# dev_board.net
KiCad netlist of a schematic drawn in EAGLE
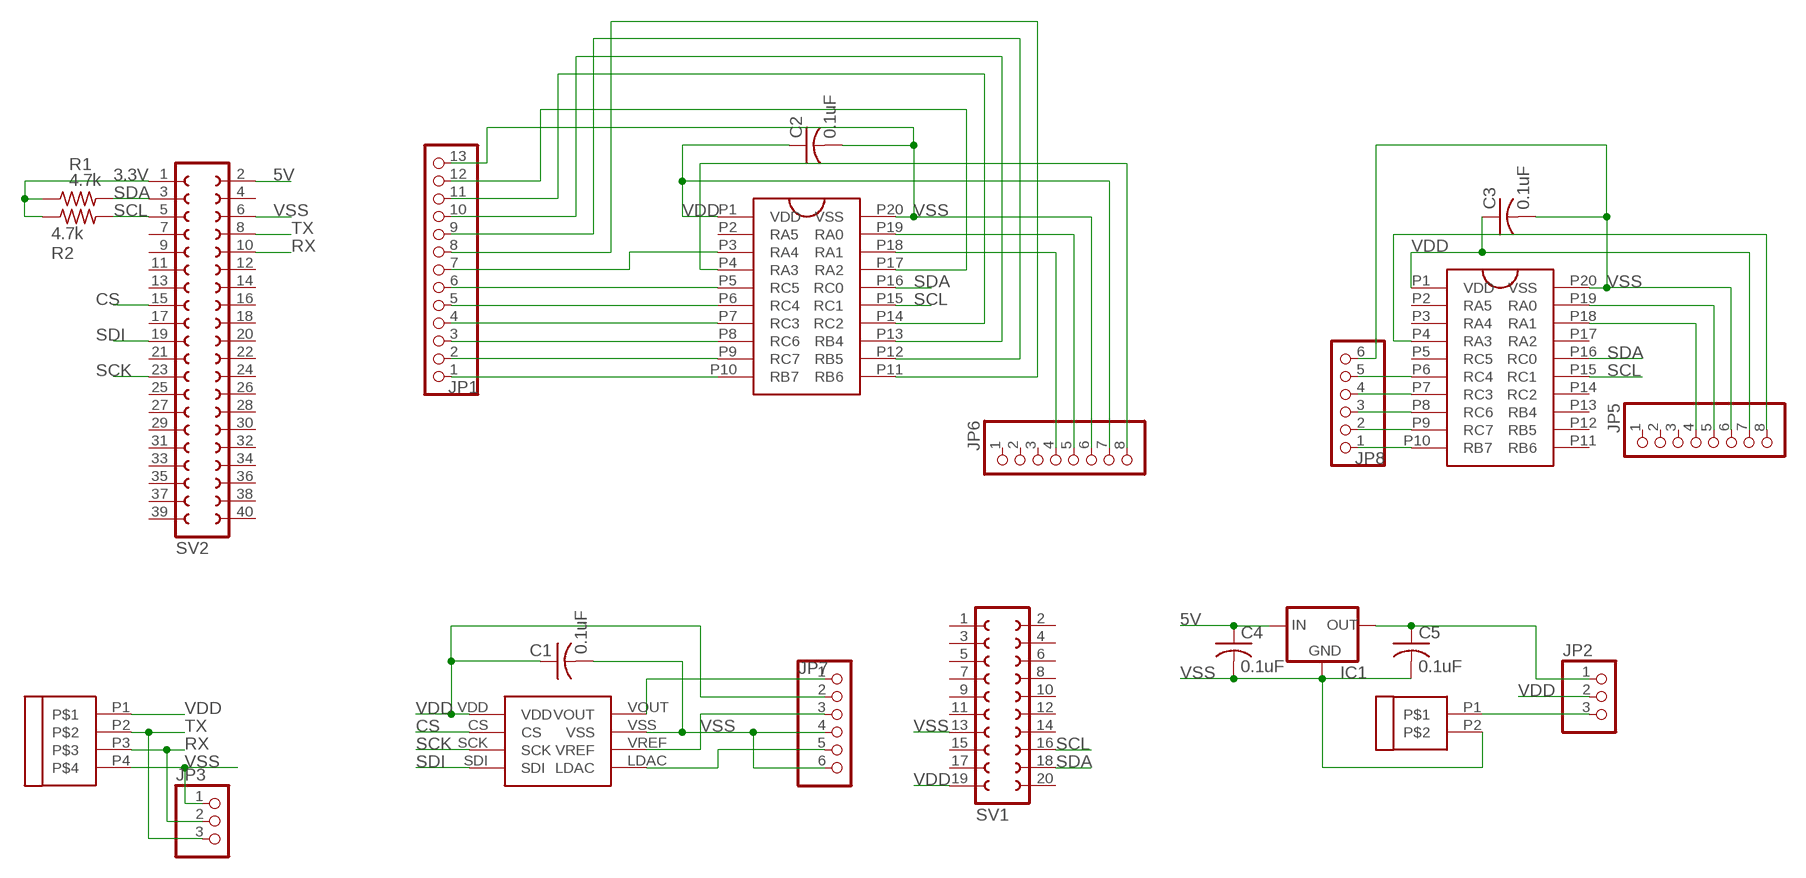
[diagram p0: schematic, sheet 1]

(export (version "E")
  (design (tool "Eeschema 10.0.6"))
  (components
    (comp (ref "C1")
      (value "0.1uF")
      (footprint "eagle-import:C025-030X050")
      (libsource (lib "eagle-import") (part "C-US025-030X050"))
    )
    (comp (ref "C2")
      (value "0.1uF")
      (footprint "eagle-import:C025-030X050")
      (libsource (lib "eagle-import") (part "C-US025-030X050"))
    )
    (comp (ref "C3")
      (value "0.1uF")
      (footprint "eagle-import:C025-030X050")
      (libsource (lib "eagle-import") (part "C-US025-030X050"))
    )
    (comp (ref "C4")
      (value "0.1uF")
      (footprint "eagle-import:C025-030X050")
      (libsource (lib "eagle-import") (part "C-US025-030X050"))
    )
    (comp (ref "C5")
      (value "0.1uF")
      (footprint "eagle-import:C025-030X050")
      (libsource (lib "eagle-import") (part "C-US025-030X050"))
    )
    (comp (ref "IC1")
      (value "MCP1700INLINE")
      (footprint "eagle-import:TO92-INLINE")
      (libsource (lib "eagle-import") (part "MCP1700INLINE"))
    )
    (comp (ref "JP1")
      (value "PINHD-1X13")
      (footprint "eagle-import:1X13")
      (libsource (lib "eagle-import") (part "PINHD-1X13"))
    )
    (comp (ref "JP2")
      (value "PINHD-1X3")
      (footprint "eagle-import:1X03")
      (libsource (lib "eagle-import") (part "PINHD-1X3"))
    )
    (comp (ref "JP3")
      (value "PINHD-1X3")
      (footprint "eagle-import:1X03")
      (libsource (lib "eagle-import") (part "pinhead_325_PINHD-1X3"))
    )
    (comp (ref "JP5")
      (value "PINHD-1X8BIG")
      (footprint "eagle-import:1X08-BIG")
      (libsource (lib "eagle-import") (part "PINHD-1X8BIG"))
    )
    (comp (ref "JP6")
      (value "PINHD-1X8BIG")
      (footprint "eagle-import:1X08-BIG")
      (libsource (lib "eagle-import") (part "PINHD-1X8BIG"))
    )
    (comp (ref "JP7")
      (value "PINHD-1X6")
      (footprint "eagle-import:1X06")
      (libsource (lib "eagle-import") (part "PINHD-1X6"))
    )
    (comp (ref "JP8")
      (value "PINHD-1X6")
      (footprint "eagle-import:1X06")
      (libsource (lib "eagle-import") (part "PINHD-1X6"))
    )
    (comp (ref "R1")
      (value "4.7k")
      (footprint "eagle-import:0207_7")
      (libsource (lib "eagle-import") (part "R-US_0207/7"))
    )
    (comp (ref "R2")
      (value "4.7k")
      (footprint "eagle-import:0207_7")
      (libsource (lib "eagle-import") (part "R-US_0207/7"))
    )
    (comp (ref "SV1")
      (value "FE10-2")
      (footprint "eagle-import:FE10-2")
      (libsource (lib "eagle-import") (part "FE10-2"))
    )
    (comp (ref "SV2")
      (value "FE20-2")
      (footprint "eagle-import:FE20-2")
      (libsource (lib "eagle-import") (part "FE20-2"))
    )
    (comp (ref "U$1")
      (value "MCP4911")
      (footprint "eagle-import:DAC_DIP")
      (libsource (lib "eagle-import") (part "MCP4911"))
    )
    (comp (ref "U$2")
      (value "4TERMBLOCK")
      (footprint "eagle-import:4TERMBLOCK")
      (libsource (lib "eagle-import") (part "4TERMBLOCK"))
    )
    (comp (ref "U$3")
      (value "2TERMBLOCK")
      (footprint "eagle-import:2TERMBLOCK")
      (libsource (lib "eagle-import") (part "2TERMBLOCK"))
    )
    (comp (ref "U1")
      (value "PIC18F15Q40PDIP")
      (footprint "eagle-import:PDIP")
      (libsource (lib "eagle-import") (part "PIC18F15Q40PDIP"))
    )
    (comp (ref "U2")
      (value "PIC18F15Q40PDIP")
      (footprint "eagle-import:PDIP")
      (libsource (lib "eagle-import") (part "PIC18F15Q40PDIP"))
    )
  )
  (nets
    (net (code "1") (name "/3.3V") (class "Default")
      (node (ref "R1") (pin "1") (pinfunction "1_1") (pintype "passive"))
      (node (ref "R2") (pin "1") (pinfunction "1_1") (pintype "passive"))
      (node (ref "SV2") (pin "1") (pinfunction "1_1") (pintype "passive"))
    )
    (net (code "2") (name "/5V") (class "Default")
      (node (ref "C4") (pin "1") (pinfunction "1_1") (pintype "passive"))
      (node (ref "IC1") (pin "2") (pinfunction "IN_2") (pintype "input"))
      (node (ref "SV2") (pin "2") (pinfunction "2_2") (pintype "passive"))
    )
    (net (code "3") (name "/CS") (class "Default")
      (node (ref "SV2") (pin "15") (pinfunction "15_15") (pintype "passive"))
      (node (ref "U$1") (pin "CS") (pinfunction "CS_CS") (pintype "bidirectional"))
    )
    (net (code "4") (name "/RX") (class "Default")
      (node (ref "JP3") (pin "2") (pinfunction "2_2") (pintype "passive"))
      (node (ref "SV2") (pin "10") (pinfunction "10_10") (pintype "passive"))
      (node (ref "U$2") (pin "P3") (pinfunction "P$3_P3") (pintype "bidirectional"))
    )
    (net (code "5") (name "/SCK") (class "Default")
      (node (ref "SV2") (pin "23") (pinfunction "23_23") (pintype "passive"))
      (node (ref "U$1") (pin "SCK") (pinfunction "SCK_SCK") (pintype "bidirectional"))
    )
    (net (code "6") (name "/SCL") (class "Default")
      (node (ref "R2") (pin "2") (pinfunction "2_2") (pintype "passive"))
      (node (ref "SV1") (pin "16") (pinfunction "16_16") (pintype "passive"))
      (node (ref "SV2") (pin "5") (pinfunction "5_5") (pintype "passive"))
      (node (ref "U1") (pin "P15") (pinfunction "RC1_P15") (pintype "bidirectional"))
      (node (ref "U2") (pin "P15") (pinfunction "RC1_P15") (pintype "bidirectional"))
    )
    (net (code "7") (name "/SDA") (class "Default")
      (node (ref "R1") (pin "2") (pinfunction "2_2") (pintype "passive"))
      (node (ref "SV1") (pin "18") (pinfunction "18_18") (pintype "passive"))
      (node (ref "SV2") (pin "3") (pinfunction "3_3") (pintype "passive"))
      (node (ref "U1") (pin "P16") (pinfunction "RC0_P16") (pintype "bidirectional"))
      (node (ref "U2") (pin "P16") (pinfunction "RC0_P16") (pintype "bidirectional"))
    )
    (net (code "8") (name "/SDI") (class "Default")
      (node (ref "SV2") (pin "19") (pinfunction "19_19") (pintype "passive"))
      (node (ref "U$1") (pin "SDI") (pinfunction "SDI_SDI") (pintype "bidirectional"))
    )
    (net (code "9") (name "/TX") (class "Default")
      (node (ref "JP3") (pin "3") (pinfunction "3_3") (pintype "passive"))
      (node (ref "SV2") (pin "8") (pinfunction "8_8") (pintype "passive"))
      (node (ref "U$2") (pin "P2") (pinfunction "P$2_P2") (pintype "bidirectional"))
    )
    (net (code "10") (name "/VDD") (class "Default")
      (node (ref "C1") (pin "1") (pinfunction "1_1") (pintype "passive"))
      (node (ref "C2") (pin "1") (pinfunction "1_1") (pintype "passive"))
      (node (ref "C3") (pin "1") (pinfunction "1_1") (pintype "passive"))
      (node (ref "JP2") (pin "2") (pinfunction "2_2") (pintype "passive"))
      (node (ref "JP5") (pin "7") (pinfunction "7_7") (pintype "passive"))
      (node (ref "JP6") (pin "7") (pinfunction "7_7") (pintype "passive"))
      (node (ref "JP7") (pin "2") (pinfunction "2_2") (pintype "passive"))
      (node (ref "SV1") (pin "19") (pinfunction "19_19") (pintype "passive"))
      (node (ref "U$1") (pin "VDD") (pinfunction "VDD_VDD") (pintype "bidirectional"))
      (node (ref "U$2") (pin "P1") (pinfunction "P$1_P1") (pintype "bidirectional"))
      (node (ref "U1") (pin "P1") (pinfunction "VDD_P1") (pintype "bidirectional"))
      (node (ref "U2") (pin "P1") (pinfunction "VDD_P1") (pintype "bidirectional"))
    )
    (net (code "11") (name "/VSS") (class "Default")
      (node (ref "C1") (pin "2") (pinfunction "2_2") (pintype "passive"))
      (node (ref "C2") (pin "2") (pinfunction "2_2") (pintype "passive"))
      (node (ref "C3") (pin "2") (pinfunction "2_2") (pintype "passive"))
      (node (ref "C4") (pin "2") (pinfunction "2_2") (pintype "passive"))
      (node (ref "C5") (pin "2") (pinfunction "2_2") (pintype "passive"))
      (node (ref "IC1") (pin "1") (pinfunction "GND_1") (pintype "input"))
      (node (ref "JP1") (pin "13") (pinfunction "13_13") (pintype "passive"))
      (node (ref "JP3") (pin "1") (pinfunction "1_1") (pintype "passive"))
      (node (ref "JP5") (pin "6") (pinfunction "6_6") (pintype "passive"))
      (node (ref "JP6") (pin "6") (pinfunction "6_6") (pintype "passive"))
      (node (ref "JP7") (pin "4") (pinfunction "4_4") (pintype "passive"))
      (node (ref "JP7") (pin "6") (pinfunction "6_6") (pintype "passive"))
      (node (ref "JP8") (pin "6") (pinfunction "6_6") (pintype "passive"))
      (node (ref "SV1") (pin "13") (pinfunction "13_13") (pintype "passive"))
      (node (ref "SV2") (pin "6") (pinfunction "6_6") (pintype "passive"))
      (node (ref "U$1") (pin "VSS") (pinfunction "VSS_VSS") (pintype "bidirectional"))
      (node (ref "U$2") (pin "P4") (pinfunction "P$4_P4") (pintype "bidirectional"))
      (node (ref "U$3") (pin "P2") (pinfunction "P$2_P2") (pintype "bidirectional"))
      (node (ref "U1") (pin "P20") (pinfunction "VSS_P20") (pintype "bidirectional"))
      (node (ref "U2") (pin "P20") (pinfunction "VSS_P20") (pintype "bidirectional"))
    )
    (net (code "12") (name "Net-(IC1-OUT)") (class "Default")
      (node (ref "C5") (pin "1") (pinfunction "1_1") (pintype "passive"))
      (node (ref "IC1") (pin "3") (pinfunction "OUT_3") (pintype "passive"))
      (node (ref "JP2") (pin "1") (pinfunction "1_1") (pintype "passive"))
    )
    (net (code "13") (name "Net-(JP7-Pad1)") (class "Default")
      (node (ref "JP7") (pin "1") (pinfunction "1_1") (pintype "passive"))
      (node (ref "U$1") (pin "VOUT") (pinfunction "VOUT_VOUT") (pintype "bidirectional"))
    )
    (net (code "14") (name "Net-(JP7-Pad3)") (class "Default")
      (node (ref "JP7") (pin "3") (pinfunction "3_3") (pintype "passive"))
      (node (ref "U$1") (pin "VREF") (pinfunction "VREF_VREF") (pintype "bidirectional"))
    )
    (net (code "15") (name "Net-(JP7-Pad5)") (class "Default")
      (node (ref "JP7") (pin "5") (pinfunction "5_5") (pintype "passive"))
      (node (ref "U$1") (pin "LDAC") (pinfunction "LDAC_LDAC") (pintype "bidirectional"))
    )
    (net (code "16") (name "Net-(U$3-P$1)") (class "Default")
      (node (ref "JP2") (pin "3") (pinfunction "3_3") (pintype "passive"))
      (node (ref "U$3") (pin "P1") (pinfunction "P$1_P1") (pintype "bidirectional"))
    )
    (net (code "17") (name "Net-(U1-RA0)") (class "Default")
      (node (ref "JP6") (pin "5") (pinfunction "5_5") (pintype "passive"))
      (node (ref "U1") (pin "P19") (pinfunction "RA0_P19") (pintype "bidirectional"))
    )
    (net (code "18") (name "Net-(U1-RA1)") (class "Default")
      (node (ref "JP6") (pin "4") (pinfunction "4_4") (pintype "passive"))
      (node (ref "U1") (pin "P18") (pinfunction "RA1_P18") (pintype "bidirectional"))
    )
    (net (code "19") (name "Net-(U1-RA2)") (class "Default")
      (node (ref "JP1") (pin "12") (pinfunction "12_12") (pintype "passive"))
      (node (ref "U1") (pin "P17") (pinfunction "RA2_P17") (pintype "bidirectional"))
    )
    (net (code "20") (name "Net-(U1-RA3)") (class "Default")
      (node (ref "JP6") (pin "8") (pinfunction "8_8") (pintype "passive"))
      (node (ref "U1") (pin "P4") (pinfunction "RA3_P4") (pintype "bidirectional"))
    )
    (net (code "21") (name "Net-(U1-RA4)") (class "Default")
      (node (ref "JP1") (pin "7") (pinfunction "7_7") (pintype "passive"))
      (node (ref "U1") (pin "P3") (pinfunction "RA4_P3") (pintype "bidirectional"))
    )
    (net (code "22") (name "Net-(U1-RB4)") (class "Default")
      (node (ref "JP1") (pin "10") (pinfunction "10_10") (pintype "passive"))
      (node (ref "U1") (pin "P13") (pinfunction "RB4_P13") (pintype "bidirectional"))
    )
    (net (code "23") (name "Net-(U1-RB5)") (class "Default")
      (node (ref "JP1") (pin "9") (pinfunction "9_9") (pintype "passive"))
      (node (ref "U1") (pin "P12") (pinfunction "RB5_P12") (pintype "bidirectional"))
    )
    (net (code "24") (name "Net-(U1-RB6)") (class "Default")
      (node (ref "JP1") (pin "8") (pinfunction "8_8") (pintype "passive"))
      (node (ref "U1") (pin "P11") (pinfunction "RB6_P11") (pintype "bidirectional"))
    )
    (net (code "25") (name "Net-(U1-RB7)") (class "Default")
      (node (ref "JP1") (pin "1") (pinfunction "1_1") (pintype "passive"))
      (node (ref "U1") (pin "P10") (pinfunction "RB7_P10") (pintype "bidirectional"))
    )
    (net (code "26") (name "Net-(U1-RC2)") (class "Default")
      (node (ref "JP1") (pin "11") (pinfunction "11_11") (pintype "passive"))
      (node (ref "U1") (pin "P14") (pinfunction "RC2_P14") (pintype "bidirectional"))
    )
    (net (code "27") (name "Net-(U1-RC3)") (class "Default")
      (node (ref "JP1") (pin "4") (pinfunction "4_4") (pintype "passive"))
      (node (ref "U1") (pin "P7") (pinfunction "RC3_P7") (pintype "bidirectional"))
    )
    (net (code "28") (name "Net-(U1-RC4)") (class "Default")
      (node (ref "JP1") (pin "5") (pinfunction "5_5") (pintype "passive"))
      (node (ref "U1") (pin "P6") (pinfunction "RC4_P6") (pintype "bidirectional"))
    )
    (net (code "29") (name "Net-(U1-RC5)") (class "Default")
      (node (ref "JP1") (pin "6") (pinfunction "6_6") (pintype "passive"))
      (node (ref "U1") (pin "P5") (pinfunction "RC5_P5") (pintype "bidirectional"))
    )
    (net (code "30") (name "Net-(U1-RC6)") (class "Default")
      (node (ref "JP1") (pin "3") (pinfunction "3_3") (pintype "passive"))
      (node (ref "U1") (pin "P8") (pinfunction "RC6_P8") (pintype "bidirectional"))
    )
    (net (code "31") (name "Net-(U1-RC7)") (class "Default")
      (node (ref "JP1") (pin "2") (pinfunction "2_2") (pintype "passive"))
      (node (ref "U1") (pin "P9") (pinfunction "RC7_P9") (pintype "bidirectional"))
    )
    (net (code "32") (name "Net-(U2-RA0)") (class "Default")
      (node (ref "JP5") (pin "5") (pinfunction "5_5") (pintype "passive"))
      (node (ref "U2") (pin "P19") (pinfunction "RA0_P19") (pintype "bidirectional"))
    )
    (net (code "33") (name "Net-(U2-RA1)") (class "Default")
      (node (ref "JP5") (pin "4") (pinfunction "4_4") (pintype "passive"))
      (node (ref "U2") (pin "P18") (pinfunction "RA1_P18") (pintype "bidirectional"))
    )
    (net (code "34") (name "Net-(U2-RA3)") (class "Default")
      (node (ref "JP5") (pin "8") (pinfunction "8_8") (pintype "passive"))
      (node (ref "U2") (pin "P4") (pinfunction "RA3_P4") (pintype "bidirectional"))
    )
    (net (code "35") (name "Net-(U2-RB7)") (class "Default")
      (node (ref "JP8") (pin "1") (pinfunction "1_1") (pintype "passive"))
      (node (ref "U2") (pin "P10") (pinfunction "RB7_P10") (pintype "bidirectional"))
    )
    (net (code "36") (name "Net-(U2-RC3)") (class "Default")
      (node (ref "JP8") (pin "4") (pinfunction "4_4") (pintype "passive"))
      (node (ref "U2") (pin "P7") (pinfunction "RC3_P7") (pintype "bidirectional"))
    )
    (net (code "37") (name "Net-(U2-RC4)") (class "Default")
      (node (ref "JP8") (pin "5") (pinfunction "5_5") (pintype "passive"))
      (node (ref "U2") (pin "P6") (pinfunction "RC4_P6") (pintype "bidirectional"))
    )
    (net (code "38") (name "Net-(U2-RC6)") (class "Default")
      (node (ref "JP8") (pin "3") (pinfunction "3_3") (pintype "passive"))
      (node (ref "U2") (pin "P8") (pinfunction "RC6_P8") (pintype "bidirectional"))
    )
    (net (code "39") (name "Net-(U2-RC7)") (class "Default")
      (node (ref "JP8") (pin "2") (pinfunction "2_2") (pintype "passive"))
      (node (ref "U2") (pin "P9") (pinfunction "RC7_P9") (pintype "bidirectional"))
    )
    (net (code "40") (name "unconnected-(JP5-Pad1)") (class "Default")
      (node (ref "JP5") (pin "1") (pinfunction "1_1") (pintype "passive"))
    )
    (net (code "41") (name "unconnected-(JP5-Pad2)") (class "Default")
      (node (ref "JP5") (pin "2") (pinfunction "2_2") (pintype "passive"))
    )
    (net (code "42") (name "unconnected-(JP5-Pad3)") (class "Default")
      (node (ref "JP5") (pin "3") (pinfunction "3_3") (pintype "passive"))
    )
    (net (code "43") (name "unconnected-(JP6-Pad1)") (class "Default")
      (node (ref "JP6") (pin "1") (pinfunction "1_1") (pintype "passive"))
    )
    (net (code "44") (name "unconnected-(JP6-Pad2)") (class "Default")
      (node (ref "JP6") (pin "2") (pinfunction "2_2") (pintype "passive"))
    )
    (net (code "45") (name "unconnected-(JP6-Pad3)") (class "Default")
      (node (ref "JP6") (pin "3") (pinfunction "3_3") (pintype "passive"))
    )
    (net (code "46") (name "unconnected-(SV1-Pad1)") (class "Default")
      (node (ref "SV1") (pin "1") (pinfunction "1_1") (pintype "passive"))
    )
    (net (code "47") (name "unconnected-(SV1-Pad2)") (class "Default")
      (node (ref "SV1") (pin "2") (pinfunction "2_2") (pintype "passive"))
    )
    (net (code "48") (name "unconnected-(SV1-Pad3)") (class "Default")
      (node (ref "SV1") (pin "3") (pinfunction "3_3") (pintype "passive"))
    )
    (net (code "49") (name "unconnected-(SV1-Pad4)") (class "Default")
      (node (ref "SV1") (pin "4") (pinfunction "4_4") (pintype "passive"))
    )
    (net (code "50") (name "unconnected-(SV1-Pad5)") (class "Default")
      (node (ref "SV1") (pin "5") (pinfunction "5_5") (pintype "passive"))
    )
    (net (code "51") (name "unconnected-(SV1-Pad6)") (class "Default")
      (node (ref "SV1") (pin "6") (pinfunction "6_6") (pintype "passive"))
    )
    (net (code "52") (name "unconnected-(SV1-Pad7)") (class "Default")
      (node (ref "SV1") (pin "7") (pinfunction "7_7") (pintype "passive"))
    )
    (net (code "53") (name "unconnected-(SV1-Pad8)") (class "Default")
      (node (ref "SV1") (pin "8") (pinfunction "8_8") (pintype "passive"))
    )
    (net (code "54") (name "unconnected-(SV1-Pad9)") (class "Default")
      (node (ref "SV1") (pin "9") (pinfunction "9_9") (pintype "passive"))
    )
    (net (code "55") (name "unconnected-(SV1-Pad10)") (class "Default")
      (node (ref "SV1") (pin "10") (pinfunction "10_10") (pintype "passive"))
    )
    (net (code "56") (name "unconnected-(SV1-Pad11)") (class "Default")
      (node (ref "SV1") (pin "11") (pinfunction "11_11") (pintype "passive"))
    )
    (net (code "57") (name "unconnected-(SV1-Pad12)") (class "Default")
      (node (ref "SV1") (pin "12") (pinfunction "12_12") (pintype "passive"))
    )
    (net (code "58") (name "unconnected-(SV1-Pad14)") (class "Default")
      (node (ref "SV1") (pin "14") (pinfunction "14_14") (pintype "passive"))
    )
    (net (code "59") (name "unconnected-(SV1-Pad15)") (class "Default")
      (node (ref "SV1") (pin "15") (pinfunction "15_15") (pintype "passive"))
    )
    (net (code "60") (name "unconnected-(SV1-Pad17)") (class "Default")
      (node (ref "SV1") (pin "17") (pinfunction "17_17") (pintype "passive"))
    )
    (net (code "61") (name "unconnected-(SV1-Pad20)") (class "Default")
      (node (ref "SV1") (pin "20") (pinfunction "20_20") (pintype "passive"))
    )
    (net (code "62") (name "unconnected-(SV2-Pad4)") (class "Default")
      (node (ref "SV2") (pin "4") (pinfunction "4_4") (pintype "passive"))
    )
    (net (code "63") (name "unconnected-(SV2-Pad7)") (class "Default")
      (node (ref "SV2") (pin "7") (pinfunction "7_7") (pintype "passive"))
    )
    (net (code "64") (name "unconnected-(SV2-Pad9)") (class "Default")
      (node (ref "SV2") (pin "9") (pinfunction "9_9") (pintype "passive"))
    )
    (net (code "65") (name "unconnected-(SV2-Pad11)") (class "Default")
      (node (ref "SV2") (pin "11") (pinfunction "11_11") (pintype "passive"))
    )
    (net (code "66") (name "unconnected-(SV2-Pad12)") (class "Default")
      (node (ref "SV2") (pin "12") (pinfunction "12_12") (pintype "passive"))
    )
    (net (code "67") (name "unconnected-(SV2-Pad13)") (class "Default")
      (node (ref "SV2") (pin "13") (pinfunction "13_13") (pintype "passive"))
    )
    (net (code "68") (name "unconnected-(SV2-Pad14)") (class "Default")
      (node (ref "SV2") (pin "14") (pinfunction "14_14") (pintype "passive"))
    )
    (net (code "69") (name "unconnected-(SV2-Pad16)") (class "Default")
      (node (ref "SV2") (pin "16") (pinfunction "16_16") (pintype "passive"))
    )
    (net (code "70") (name "unconnected-(SV2-Pad17)") (class "Default")
      (node (ref "SV2") (pin "17") (pinfunction "17_17") (pintype "passive"))
    )
    (net (code "71") (name "unconnected-(SV2-Pad18)") (class "Default")
      (node (ref "SV2") (pin "18") (pinfunction "18_18") (pintype "passive"))
    )
    (net (code "72") (name "unconnected-(SV2-Pad20)") (class "Default")
      (node (ref "SV2") (pin "20") (pinfunction "20_20") (pintype "passive"))
    )
    (net (code "73") (name "unconnected-(SV2-Pad21)") (class "Default")
      (node (ref "SV2") (pin "21") (pinfunction "21_21") (pintype "passive"))
    )
    (net (code "74") (name "unconnected-(SV2-Pad22)") (class "Default")
      (node (ref "SV2") (pin "22") (pinfunction "22_22") (pintype "passive"))
    )
    (net (code "75") (name "unconnected-(SV2-Pad24)") (class "Default")
      (node (ref "SV2") (pin "24") (pinfunction "24_24") (pintype "passive"))
    )
    (net (code "76") (name "unconnected-(SV2-Pad25)") (class "Default")
      (node (ref "SV2") (pin "25") (pinfunction "25_25") (pintype "passive"))
    )
    (net (code "77") (name "unconnected-(SV2-Pad26)") (class "Default")
      (node (ref "SV2") (pin "26") (pinfunction "26_26") (pintype "passive"))
    )
    (net (code "78") (name "unconnected-(SV2-Pad27)") (class "Default")
      (node (ref "SV2") (pin "27") (pinfunction "27_27") (pintype "passive"))
    )
    (net (code "79") (name "unconnected-(SV2-Pad28)") (class "Default")
      (node (ref "SV2") (pin "28") (pinfunction "28_28") (pintype "passive"))
    )
    (net (code "80") (name "unconnected-(SV2-Pad29)") (class "Default")
      (node (ref "SV2") (pin "29") (pinfunction "29_29") (pintype "passive"))
    )
    (net (code "81") (name "unconnected-(SV2-Pad30)") (class "Default")
      (node (ref "SV2") (pin "30") (pinfunction "30_30") (pintype "passive"))
    )
    (net (code "82") (name "unconnected-(SV2-Pad31)") (class "Default")
      (node (ref "SV2") (pin "31") (pinfunction "31_31") (pintype "passive"))
    )
    (net (code "83") (name "unconnected-(SV2-Pad32)") (class "Default")
      (node (ref "SV2") (pin "32") (pinfunction "32_32") (pintype "passive"))
    )
    (net (code "84") (name "unconnected-(SV2-Pad33)") (class "Default")
      (node (ref "SV2") (pin "33") (pinfunction "33_33") (pintype "passive"))
    )
    (net (code "85") (name "unconnected-(SV2-Pad34)") (class "Default")
      (node (ref "SV2") (pin "34") (pinfunction "34_34") (pintype "passive"))
    )
    (net (code "86") (name "unconnected-(SV2-Pad35)") (class "Default")
      (node (ref "SV2") (pin "35") (pinfunction "35_35") (pintype "passive"))
    )
    (net (code "87") (name "unconnected-(SV2-Pad36)") (class "Default")
      (node (ref "SV2") (pin "36") (pinfunction "36_36") (pintype "passive"))
    )
    (net (code "88") (name "unconnected-(SV2-Pad37)") (class "Default")
      (node (ref "SV2") (pin "37") (pinfunction "37_37") (pintype "passive"))
    )
    (net (code "89") (name "unconnected-(SV2-Pad38)") (class "Default")
      (node (ref "SV2") (pin "38") (pinfunction "38_38") (pintype "passive"))
    )
    (net (code "90") (name "unconnected-(SV2-Pad39)") (class "Default")
      (node (ref "SV2") (pin "39") (pinfunction "39_39") (pintype "passive"))
    )
    (net (code "91") (name "unconnected-(SV2-Pad40)") (class "Default")
      (node (ref "SV2") (pin "40") (pinfunction "40_40") (pintype "passive"))
    )
    (net (code "92") (name "unconnected-(U1-RA5-PadP2)") (class "Default")
      (node (ref "U1") (pin "P2") (pinfunction "RA5_P2") (pintype "bidirectional"))
    )
    (net (code "93") (name "unconnected-(U2-RA2-PadP17)") (class "Default")
      (node (ref "U2") (pin "P17") (pinfunction "RA2_P17") (pintype "bidirectional"))
    )
    (net (code "94") (name "unconnected-(U2-RA4-PadP3)") (class "Default")
      (node (ref "U2") (pin "P3") (pinfunction "RA4_P3") (pintype "bidirectional"))
    )
    (net (code "95") (name "unconnected-(U2-RA5-PadP2)") (class "Default")
      (node (ref "U2") (pin "P2") (pinfunction "RA5_P2") (pintype "bidirectional"))
    )
    (net (code "96") (name "unconnected-(U2-RB4-PadP13)") (class "Default")
      (node (ref "U2") (pin "P13") (pinfunction "RB4_P13") (pintype "bidirectional"))
    )
    (net (code "97") (name "unconnected-(U2-RB5-PadP12)") (class "Default")
      (node (ref "U2") (pin "P12") (pinfunction "RB5_P12") (pintype "bidirectional"))
    )
    (net (code "98") (name "unconnected-(U2-RB6-PadP11)") (class "Default")
      (node (ref "U2") (pin "P11") (pinfunction "RB6_P11") (pintype "bidirectional"))
    )
    (net (code "99") (name "unconnected-(U2-RC2-PadP14)") (class "Default")
      (node (ref "U2") (pin "P14") (pinfunction "RC2_P14") (pintype "bidirectional"))
    )
    (net (code "100") (name "unconnected-(U2-RC5-PadP5)") (class "Default")
      (node (ref "U2") (pin "P5") (pinfunction "RC5_P5") (pintype "bidirectional"))
    )
  )
)
